# ControllerV1_0_1.net
KiCad netlist of a schematic drawn in Altium Designer
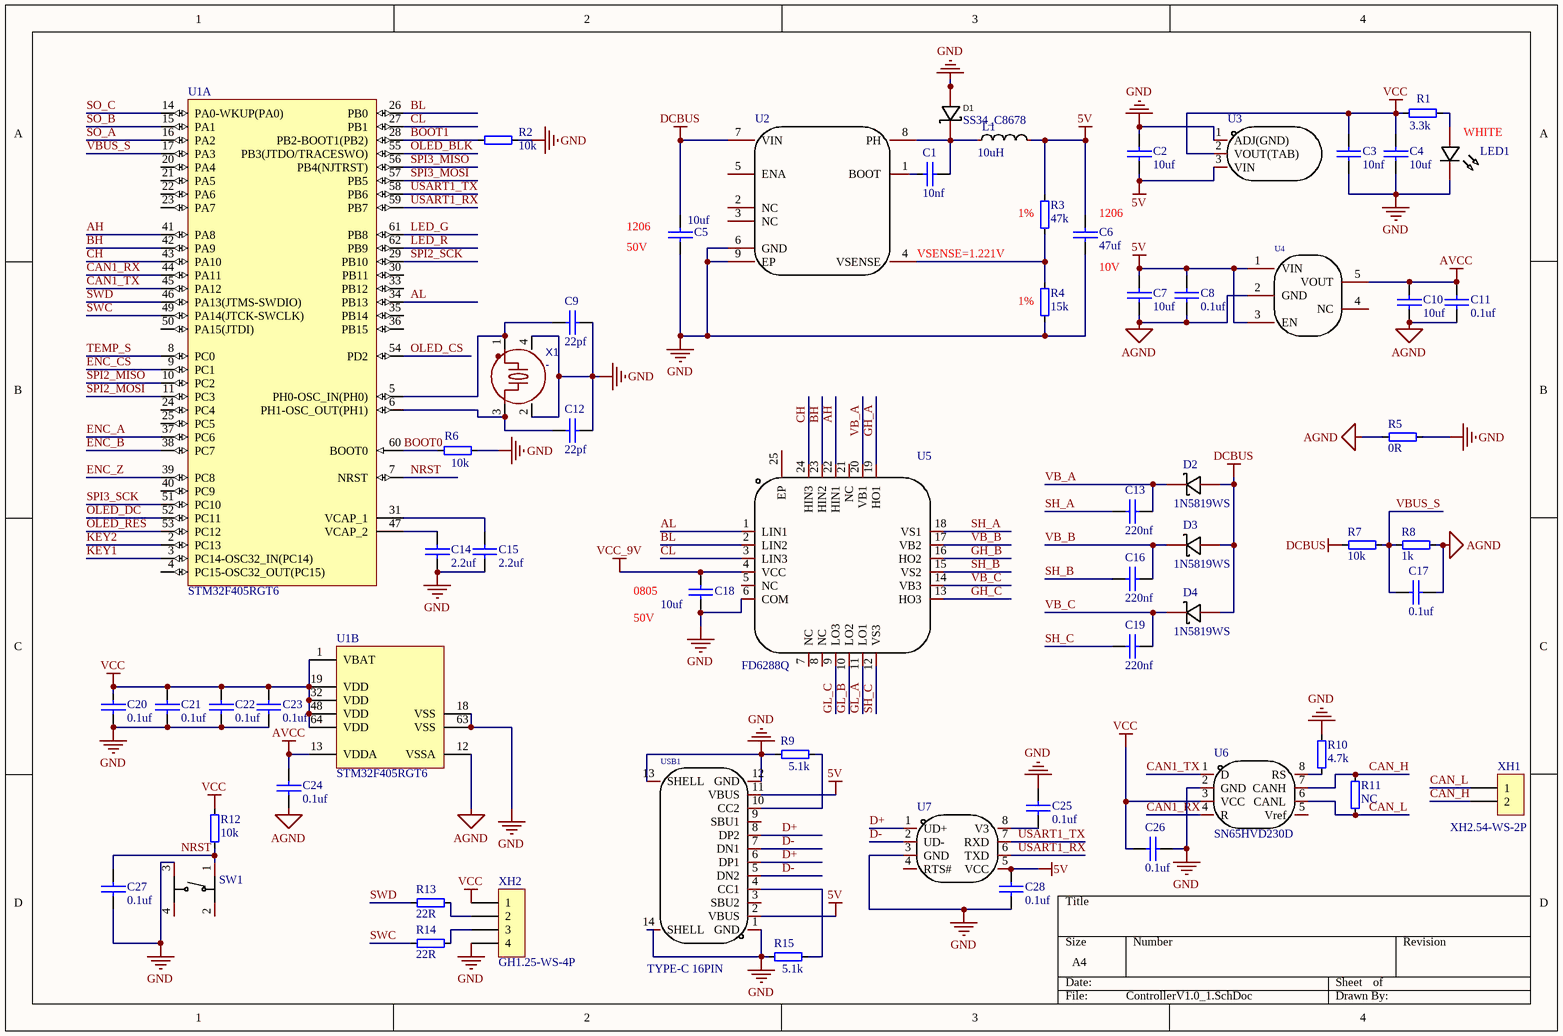
[diagram p0: ControllerV1.0_1.SchDoc]

(export (version "E")
  (design (tool "Eeschema 10.0.6"))
  (components
    (comp (ref "C1")
      (value "10nf")
      (footprint "0603C")
      (description "贴片电容")
      (libsource (lib "Controller") (part "CAP"))
    )
    (comp (ref "C2")
      (value "10uf")
      (footprint "0603C")
      (description "贴片电容")
      (libsource (lib "Controller") (part "CAP"))
    )
    (comp (ref "C3")
      (value "10nf")
      (footprint "0603C")
      (description "贴片电容")
      (libsource (lib "Controller") (part "CAP"))
    )
    (comp (ref "C4")
      (value "10uf")
      (footprint "0603C")
      (description "贴片电容")
      (libsource (lib "Controller") (part "CAP"))
    )
    (comp (ref "C5")
      (value "10uf")
      (footprint "1206C")
      (description "贴片电容")
      (libsource (lib "Controller") (part "CAP"))
    )
    (comp (ref "C6")
      (value "47uf")
      (footprint "1206C")
      (description "贴片电容")
      (libsource (lib "Controller") (part "CAP"))
    )
    (comp (ref "C7")
      (value "10uf")
      (footprint "0603C")
      (description "贴片电容")
      (libsource (lib "Controller") (part "CAP"))
    )
    (comp (ref "C8")
      (value "0.1uf")
      (footprint "0603C")
      (description "贴片电容")
      (libsource (lib "Controller") (part "CAP"))
    )
    (comp (ref "C9")
      (value "22pf")
      (footprint "0603C")
      (description "贴片电容")
      (libsource (lib "Controller") (part "CAP"))
    )
    (comp (ref "C10")
      (value "10uf")
      (footprint "0603C")
      (description "贴片电容")
      (libsource (lib "Controller") (part "CAP"))
    )
    (comp (ref "C11")
      (value "0.1uf")
      (footprint "0603C")
      (description "贴片电容")
      (libsource (lib "Controller") (part "CAP"))
    )
    (comp (ref "C12")
      (value "22pf")
      (footprint "0603C")
      (description "贴片电容")
      (libsource (lib "Controller") (part "CAP"))
    )
    (comp (ref "C13")
      (value "220nf")
      (footprint "0603C")
      (description "贴片电容")
      (libsource (lib "Controller") (part "CAP"))
    )
    (comp (ref "C14")
      (value "2.2uf")
      (footprint "0603C")
      (description "贴片电容")
      (libsource (lib "Controller") (part "CAP"))
    )
    (comp (ref "C15")
      (value "2.2uf")
      (footprint "0603C")
      (description "贴片电容")
      (libsource (lib "Controller") (part "CAP"))
    )
    (comp (ref "C16")
      (value "220nf")
      (footprint "0603C")
      (description "贴片电容")
      (libsource (lib "Controller") (part "CAP"))
    )
    (comp (ref "C17")
      (value "0.1uf")
      (footprint "0603C")
      (description "贴片电容")
      (libsource (lib "Controller") (part "CAP"))
    )
    (comp (ref "C18")
      (value "10uf")
      (footprint "0805C")
      (description "贴片电容")
      (libsource (lib "Controller") (part "CAP"))
    )
    (comp (ref "C19")
      (value "220nf")
      (footprint "0603C")
      (description "贴片电容")
      (libsource (lib "Controller") (part "CAP"))
    )
    (comp (ref "C20")
      (value "0.1uf")
      (footprint "0603C")
      (description "贴片电容")
      (libsource (lib "Controller") (part "CAP"))
    )
    (comp (ref "C21")
      (value "0.1uf")
      (footprint "0603C")
      (description "贴片电容")
      (libsource (lib "Controller") (part "CAP"))
    )
    (comp (ref "C22")
      (value "0.1uf")
      (footprint "0603C")
      (description "贴片电容")
      (libsource (lib "Controller") (part "CAP"))
    )
    (comp (ref "C23")
      (value "0.1uf")
      (footprint "0603C")
      (description "贴片电容")
      (libsource (lib "Controller") (part "CAP"))
    )
    (comp (ref "C24")
      (value "0.1uf")
      (footprint "0603C")
      (description "贴片电容")
      (libsource (lib "Controller") (part "CAP"))
    )
    (comp (ref "C25")
      (value "0.1uf")
      (footprint "0603C")
      (description "贴片电容")
      (libsource (lib "Controller") (part "CAP"))
    )
    (comp (ref "C26")
      (value "0.1uf")
      (footprint "0603C")
      (description "贴片电容")
      (libsource (lib "Controller") (part "CAP"))
    )
    (comp (ref "C27")
      (value "0.1uf")
      (footprint "0603C")
      (description "贴片电容")
      (libsource (lib "Controller") (part "CAP"))
    )
    (comp (ref "C28")
      (value "0.1uf")
      (footprint "0603C")
      (description "贴片电容")
      (libsource (lib "Controller") (part "CAP"))
    )
    (comp (ref "D1")
      (value "SS34_C8678")
      (footprint "SS34")
      (description "肖特基二极管")
      (fields (field (name "MANUFACTURER") "MDD") (field (name "MANUFACTURER PART") "SS34"))
      (libsource (lib "Controller") (part "SS34"))
    )
    (comp (ref "D2")
      (value "1N5819WS")
      (footprint "SOD-323")
      (description "肖特基二极管")
      (fields (field (name "MANUFACTURER") "Hottech(合科泰)"))
      (libsource (lib "Controller") (part "1N5819WS"))
    )
    (comp (ref "D3")
      (value "1N5819WS")
      (footprint "SOD-323")
      (description "肖特基二极管")
      (fields (field (name "MANUFACTURER") "Hottech(合科泰)"))
      (libsource (lib "Controller") (part "1N5819WS"))
    )
    (comp (ref "D4")
      (value "1N5819WS")
      (footprint "SOD-323")
      (description "肖特基二极管")
      (fields (field (name "MANUFACTURER") "Hottech(合科泰)"))
      (libsource (lib "Controller") (part "1N5819WS"))
    )
    (comp (ref "L1")
      (value "10uH")
      (footprint "IND-SMD_L3.0-W3.0_SWPA3010S")
      (description "电感值:10uH;精度:±20%;额定电流:920mA;")
      (fields (field (name "MANUFACTURER") "SXN(顺翔诺)") (field (name "MANUFACTURER PART") "SMDRI74-220M"))
      (libsource (lib "Controller") (part "SWPA3015S100MT"))
    )
    (comp (ref "LED1")
      (value "LED_0603-B")
      (footprint "LED_0603")
      (libsource (lib "Controller") (part "LED"))
    )
    (comp (ref "R1")
      (value "3.3k")
      (footprint "0603R")
      (description "贴片电阻")
      (libsource (lib "Controller") (part "RES"))
    )
    (comp (ref "R2")
      (value "10k")
      (footprint "0603R")
      (description "贴片电阻")
      (libsource (lib "Controller") (part "RES"))
    )
    (comp (ref "R3")
      (value "47k")
      (footprint "0603R")
      (description "贴片电阻")
      (libsource (lib "Controller") (part "RES"))
    )
    (comp (ref "R4")
      (value "15k")
      (footprint "0603R")
      (description "贴片电阻")
      (libsource (lib "Controller") (part "RES"))
    )
    (comp (ref "R5")
      (value "0R")
      (footprint "0603R")
      (description "贴片电阻")
      (libsource (lib "Controller") (part "RES"))
    )
    (comp (ref "R6")
      (value "10k")
      (footprint "0603R")
      (description "贴片电阻")
      (libsource (lib "Controller") (part "RES"))
    )
    (comp (ref "R7")
      (value "10k")
      (footprint "0603R")
      (description "贴片电阻")
      (libsource (lib "Controller") (part "RES"))
    )
    (comp (ref "R8")
      (value "1k")
      (footprint "0603R")
      (description "贴片电阻")
      (libsource (lib "Controller") (part "RES"))
    )
    (comp (ref "R9")
      (value "5.1k")
      (footprint "0603R")
      (description "贴片电阻")
      (libsource (lib "Controller") (part "RES"))
    )
    (comp (ref "R10")
      (value "4.7k")
      (footprint "0603R")
      (description "贴片电阻")
      (libsource (lib "Controller") (part "RES"))
    )
    (comp (ref "R11")
      (value "NC")
      (footprint "0603R")
      (description "贴片电阻")
      (libsource (lib "Controller") (part "RES"))
    )
    (comp (ref "R12")
      (value "10k")
      (footprint "0603R")
      (description "贴片电阻")
      (libsource (lib "Controller") (part "RES"))
    )
    (comp (ref "R13")
      (value "22R")
      (footprint "0603R")
      (description "贴片电阻")
      (libsource (lib "Controller") (part "RES"))
    )
    (comp (ref "R14")
      (value "22R")
      (footprint "0603R")
      (description "贴片电阻")
      (libsource (lib "Controller") (part "RES"))
    )
    (comp (ref "R15")
      (value "5.1k")
      (footprint "0603R")
      (description "贴片电阻")
      (libsource (lib "Controller") (part "RES"))
    )
    (comp (ref "SW1")
      (value "TS-1187A-B-A-B")
      (footprint "TSW SMD-4*4*1.5")
      (description "轻触开关")
      (fields (field (name "MANUFACTURER") "XKB Connectivity(中国星坤)"))
      (libsource (lib "Controller") (part "TS-1187A-B-A-B"))
    )
    (comp (ref "U1")
      (value "STM32F405RGT6")
      (footprint "LQFP_64")
      (fields (field (name "MANUFACTURER") "STMicroelectronics"))
      (libsource (lib "Controller") (part "STM32F405RGT6"))
    )
    (comp (ref "U2")
      (value "TPS5450DDAR")
      (footprint "SOP-8-EP")
      (fields (field (name "MANUFACTURER") "TI(德州仪器)"))
      (libsource (lib "Controller") (part "TPS5450DDAR"))
    )
    (comp (ref "U3")
      (value "AMS1117-3.3_C347256")
      (footprint "SOT-89")
      (description "输出类型:固定;输出极性:正;最大输入电压:18V;输出电压:3.3V;输出电流:1A;电源纹波抑制比(PSRR):60dB@(120Hz);")
      (fields (field (name "MANUFACTURER") "UMW(友台半导体)") (field (name "MANUFACTURER PART") "AMS1117-3.3"))
      (libsource (lib "Controller") (part "AMS1117-3.3_C347256"))
    )
    (comp (ref "U4")
      (value "RT9013-33GB")
      (footprint "SOT-23-5")
      (description "输出类型:固定;输出极性:正;最大输入电压:5.5V;输出电压:3.3V;输出电流:500mA;电源纹波抑制比(PSRR):50dB@(10kHz);")
      (fields (field (name "MANUFACTURER") "RICHTEK(立锜)"))
      (libsource (lib "Controller") (part "RT9013-33GB"))
    )
    (comp (ref "U5")
      (value "FD6288Q")
      (footprint "QFN-24-EP(4x4)")
      (fields (field (name "MANUFACTURER") "Fortior Tech(峰岹)"))
      (libsource (lib "Controller") (part "FD6288Q"))
    )
    (comp (ref "U6")
      (value "SN65HVD230D")
      (footprint "SOP-8")
      (description "具有待机模式的 3.3V CAN 收发器 8-SOIC -40 to 85")
      (fields (field (name "MANUFACTURER") "TI(德州仪器)"))
      (libsource (lib "Controller") (part "SN65HVD230D"))
    )
    (comp (ref "U7")
      (value "CH340N")
      (footprint "SOP-8")
      (fields (field (name "MANUFACTURER") "WCH(南京沁恒)"))
      (libsource (lib "Controller") (part "CH340N"))
    )
    (comp (ref "USB1")
      (value "TYPE-C 16PIN")
      (footprint "USB-C-SMD_TYPE-C-6PIN-2MD-073")
      (description "连接器类型:Type-C;标准:-;公母:母座;触点数量:16;端口数量:1;安装方式:卧贴;额定电流 - 电源:5A;工作温度范围:-25℃~+85℃;")
      (fields
        (field (name "MANUFACTURER") "SHOU HAN(首韩)")
        (field (name "MANUFACTURER PART") "TYPE-C 16PIN 2MD(073)")
      )
      (libsource (lib "Controller") (part "TYPE-C 16PIN 2MD(073)"))
    )
    (comp (ref "X1")
      (value "-")
      (footprint "OSC 2520-4P")
      (description "8MHz")
      (fields
        (field (name "BOM_SUPPLIER PART") "C843260")
        (field (name "BOM_MANUFACTURER PART") "NX2016SA-32MHZ-STD-CZS-5")
        (field (name "CONTRIBUTOR") "LCSC")
      )
      (libsource (lib "Controller") (part "四脚晶振"))
    )
    (comp (ref "XH1")
      (value "XH2.54-WS-2P")
      (footprint "XH2.54-WS-2P")
      (libsource (lib "Controller") (part "XH2.54-WS-2P"))
    )
    (comp (ref "XH2")
      (value "GH1.25-WS-4P")
      (footprint "GH1.25-WS-4P")
      (libsource (lib "Controller") (part "GH1.25-WS-4P"))
    )
  )
  (nets
    (net (code "1") (name "/AH") (class "Default")
      (node (ref "U1") (pin "41") (pinfunction "PA8_41") (pintype "bidirectional"))
      (node (ref "U5") (pin "22") (pinfunction "HIN1_22") (pintype "passive"))
    )
    (net (code "2") (name "/AL") (class "Default")
      (node (ref "U1") (pin "34") (pinfunction "PB13_34") (pintype "bidirectional"))
      (node (ref "U5") (pin "1") (pinfunction "LIN1_1") (pintype "passive"))
    )
    (net (code "3") (name "/BH") (class "Default")
      (node (ref "U1") (pin "42") (pinfunction "PA9_42") (pintype "bidirectional"))
      (node (ref "U5") (pin "23") (pinfunction "HIN2_23") (pintype "passive"))
    )
    (net (code "4") (name "/BL") (class "Default")
      (node (ref "U1") (pin "26") (pinfunction "PB0_26") (pintype "bidirectional"))
      (node (ref "U5") (pin "2") (pinfunction "LIN2_2") (pintype "passive"))
    )
    (net (code "5") (name "/BOOT0") (class "Default")
      (node (ref "R6") (pin "1") (pinfunction "1_1") (pintype "passive"))
      (node (ref "U1") (pin "60") (pinfunction "BOOT0_60") (pintype "input"))
    )
    (net (code "6") (name "/BOOT1") (class "Default")
      (node (ref "R2") (pin "1") (pinfunction "1_1") (pintype "passive"))
      (node (ref "U1") (pin "28") (pinfunction "PB2-BOOT1(PB2)_28") (pintype "bidirectional"))
    )
    (net (code "7") (name "/CAN1_RX") (class "Default")
      (node (ref "U1") (pin "44") (pinfunction "PA11_44") (pintype "bidirectional"))
      (node (ref "U6") (pin "4") (pinfunction "R_4") (pintype "passive"))
    )
    (net (code "8") (name "/CAN1_TX") (class "Default")
      (node (ref "U1") (pin "45") (pinfunction "PA12_45") (pintype "bidirectional"))
      (node (ref "U6") (pin "1") (pinfunction "D_1") (pintype "passive"))
    )
    (net (code "9") (name "/CAN_H") (class "Default")
      (node (ref "R11") (pin "2") (pinfunction "2_2") (pintype "passive"))
      (node (ref "U6") (pin "7") (pinfunction "CANH_7") (pintype "passive"))
      (node (ref "XH1") (pin "2") (pinfunction "2_2") (pintype "passive"))
    )
    (net (code "10") (name "/CAN_L") (class "Default")
      (node (ref "R11") (pin "1") (pinfunction "1_1") (pintype "passive"))
      (node (ref "U6") (pin "6") (pinfunction "CANL_6") (pintype "passive"))
      (node (ref "XH1") (pin "1") (pinfunction "1_1") (pintype "passive"))
    )
    (net (code "11") (name "/CH") (class "Default")
      (node (ref "U1") (pin "43") (pinfunction "PA10_43") (pintype "bidirectional"))
      (node (ref "U5") (pin "24") (pinfunction "HIN3_24") (pintype "passive"))
    )
    (net (code "12") (name "/CL") (class "Default")
      (node (ref "U1") (pin "27") (pinfunction "PB1_27") (pintype "bidirectional"))
      (node (ref "U5") (pin "3") (pinfunction "LIN3_3") (pintype "passive"))
    )
    (net (code "13") (name "/D+") (class "Default")
      (node (ref "U7") (pin "1") (pinfunction "UD+_1") (pintype "passive"))
      (node (ref "USB1") (pin "6") (pinfunction "DP1_6") (pintype "passive"))
      (node (ref "USB1") (pin "8") (pinfunction "DP2_8") (pintype "passive"))
    )
    (net (code "14") (name "/D-") (class "Default")
      (node (ref "U7") (pin "2") (pinfunction "UD-_2") (pintype "passive"))
      (node (ref "USB1") (pin "5") (pinfunction "DN2_5") (pintype "passive"))
      (node (ref "USB1") (pin "7") (pinfunction "DN1_7") (pintype "passive"))
    )
    (net (code "15") (name "/ENC_A") (class "Default")
      (node (ref "U1") (pin "37") (pinfunction "PC6_37") (pintype "bidirectional"))
    )
    (net (code "16") (name "/ENC_B") (class "Default")
      (node (ref "U1") (pin "38") (pinfunction "PC7_38") (pintype "bidirectional"))
    )
    (net (code "17") (name "/ENC_CS") (class "Default")
      (node (ref "U1") (pin "9") (pinfunction "PC1_9") (pintype "bidirectional"))
    )
    (net (code "18") (name "/ENC_Z") (class "Default")
      (node (ref "U1") (pin "39") (pinfunction "PC8_39") (pintype "bidirectional"))
    )
    (net (code "19") (name "/GH_A") (class "Default")
      (node (ref "U5") (pin "19") (pinfunction "HO1_19") (pintype "passive"))
    )
    (net (code "20") (name "/GH_B") (class "Default")
      (node (ref "U5") (pin "16") (pinfunction "HO2_16") (pintype "passive"))
    )
    (net (code "21") (name "/GH_C") (class "Default")
      (node (ref "U5") (pin "13") (pinfunction "HO3_13") (pintype "passive"))
    )
    (net (code "22") (name "/GL_A") (class "Default")
      (node (ref "U5") (pin "11") (pinfunction "LO1_11") (pintype "passive"))
    )
    (net (code "23") (name "/GL_B") (class "Default")
      (node (ref "U5") (pin "10") (pinfunction "LO2_10") (pintype "passive"))
    )
    (net (code "24") (name "/GL_C") (class "Default")
      (node (ref "U5") (pin "9") (pinfunction "LO3_9") (pintype "passive"))
    )
    (net (code "25") (name "/KEY1") (class "Default")
      (node (ref "U1") (pin "3") (pinfunction "PC14-OSC32_IN(PC14)_3") (pintype "bidirectional"))
    )
    (net (code "26") (name "/KEY2") (class "Default")
      (node (ref "U1") (pin "2") (pinfunction "PC13_2") (pintype "bidirectional"))
    )
    (net (code "27") (name "/LED_G") (class "Default")
      (node (ref "U1") (pin "61") (pinfunction "PB8_61") (pintype "bidirectional"))
    )
    (net (code "28") (name "/LED_R") (class "Default")
      (node (ref "U1") (pin "62") (pinfunction "PB9_62") (pintype "bidirectional"))
    )
    (net (code "29") (name "/NRST") (class "Default")
      (node (ref "C27") (pin "1") (pinfunction "1_1") (pintype "passive"))
      (node (ref "R12") (pin "1") (pinfunction "1_1") (pintype "passive"))
      (node (ref "SW1") (pin "1") (pinfunction "A_1") (pintype "passive"))
      (node (ref "U1") (pin "7") (pinfunction "NRST_7") (pintype "bidirectional"))
    )
    (net (code "30") (name "/OLED_BLK") (class "Default")
      (node (ref "U1") (pin "55") (pinfunction "PB3(JTDO/TRACESWO)_55") (pintype "bidirectional"))
    )
    (net (code "31") (name "/OLED_CS") (class "Default")
      (node (ref "U1") (pin "54") (pinfunction "PD2_54") (pintype "bidirectional"))
    )
    (net (code "32") (name "/OLED_DC") (class "Default")
      (node (ref "U1") (pin "52") (pinfunction "PC11_52") (pintype "bidirectional"))
    )
    (net (code "33") (name "/OLED_RES") (class "Default")
      (node (ref "U1") (pin "53") (pinfunction "PC12_53") (pintype "bidirectional"))
    )
    (net (code "34") (name "/SH_A") (class "Default")
      (node (ref "C13") (pin "1") (pinfunction "1_1") (pintype "passive"))
      (node (ref "U5") (pin "18") (pinfunction "VS1_18") (pintype "passive"))
    )
    (net (code "35") (name "/SH_B") (class "Default")
      (node (ref "C16") (pin "1") (pinfunction "1_1") (pintype "passive"))
      (node (ref "U5") (pin "15") (pinfunction "VS2_15") (pintype "passive"))
    )
    (net (code "36") (name "/SH_C") (class "Default")
      (node (ref "C19") (pin "1") (pinfunction "1_1") (pintype "passive"))
      (node (ref "U5") (pin "12") (pinfunction "VS3_12") (pintype "passive"))
    )
    (net (code "37") (name "/SO_A") (class "Default")
      (node (ref "U1") (pin "16") (pinfunction "PA2_16") (pintype "bidirectional"))
    )
    (net (code "38") (name "/SO_B") (class "Default")
      (node (ref "U1") (pin "15") (pinfunction "PA1_15") (pintype "bidirectional"))
    )
    (net (code "39") (name "/SO_C") (class "Default")
      (node (ref "U1") (pin "14") (pinfunction "PA0-WKUP(PA0)_14") (pintype "bidirectional"))
    )
    (net (code "40") (name "/SPI2_MISO") (class "Default")
      (node (ref "U1") (pin "10") (pinfunction "PC2_10") (pintype "bidirectional"))
    )
    (net (code "41") (name "/SPI2_MOSI") (class "Default")
      (node (ref "U1") (pin "11") (pinfunction "PC3_11") (pintype "bidirectional"))
    )
    (net (code "42") (name "/SPI2_SCK") (class "Default")
      (node (ref "U1") (pin "29") (pinfunction "PB10_29") (pintype "bidirectional"))
    )
    (net (code "43") (name "/SPI3_MISO") (class "Default")
      (node (ref "U1") (pin "56") (pinfunction "PB4(NJTRST)_56") (pintype "bidirectional"))
    )
    (net (code "44") (name "/SPI3_MOSI") (class "Default")
      (node (ref "U1") (pin "57") (pinfunction "PB5_57") (pintype "bidirectional"))
    )
    (net (code "45") (name "/SPI3_SCK") (class "Default")
      (node (ref "U1") (pin "51") (pinfunction "PC10_51") (pintype "bidirectional"))
    )
    (net (code "46") (name "/SWC") (class "Default")
      (node (ref "R14") (pin "1") (pinfunction "1_1") (pintype "passive"))
      (node (ref "U1") (pin "49") (pinfunction "PA14(JTCK-SWCLK)_49") (pintype "bidirectional"))
    )
    (net (code "47") (name "/SWD") (class "Default")
      (node (ref "R13") (pin "1") (pinfunction "1_1") (pintype "passive"))
      (node (ref "U1") (pin "46") (pinfunction "PA13(JTMS-SWDIO)_46") (pintype "bidirectional"))
    )
    (net (code "48") (name "/TEMP_S") (class "Default")
      (node (ref "U1") (pin "8") (pinfunction "PC0_8") (pintype "bidirectional"))
    )
    (net (code "49") (name "/USART1_RX") (class "Default")
      (node (ref "U1") (pin "59") (pinfunction "PB7_59") (pintype "bidirectional"))
      (node (ref "U7") (pin "6") (pinfunction "TXD_6") (pintype "passive"))
    )
    (net (code "50") (name "/USART1_TX") (class "Default")
      (node (ref "U1") (pin "58") (pinfunction "PB6_58") (pintype "bidirectional"))
      (node (ref "U7") (pin "7") (pinfunction "RXD_7") (pintype "passive"))
    )
    (net (code "51") (name "/VBUS_S") (class "Default")
      (node (ref "C17") (pin "1") (pinfunction "1_1") (pintype "passive"))
      (node (ref "R7") (pin "1") (pinfunction "1_1") (pintype "passive"))
      (node (ref "R8") (pin "2") (pinfunction "2_2") (pintype "passive"))
      (node (ref "U1") (pin "17") (pinfunction "PA3_17") (pintype "bidirectional"))
    )
    (net (code "52") (name "/VB_A") (class "Default")
      (node (ref "C13") (pin "2") (pinfunction "2_2") (pintype "passive"))
      (node (ref "D2") (pin "1") (pinfunction "K_1") (pintype "passive"))
      (node (ref "U5") (pin "20") (pinfunction "VB1_20") (pintype "passive"))
    )
    (net (code "53") (name "/VB_B") (class "Default")
      (node (ref "C16") (pin "2") (pinfunction "2_2") (pintype "passive"))
      (node (ref "D3") (pin "1") (pinfunction "K_1") (pintype "passive"))
      (node (ref "U5") (pin "17") (pinfunction "VB2_17") (pintype "passive"))
    )
    (net (code "54") (name "/VB_C") (class "Default")
      (node (ref "C19") (pin "2") (pinfunction "2_2") (pintype "passive"))
      (node (ref "D4") (pin "1") (pinfunction "K_1") (pintype "passive"))
      (node (ref "U5") (pin "14") (pinfunction "VB3_14") (pintype "passive"))
    )
    (net (code "55") (name "5V") (class "Default")
      (node (ref "C2") (pin "2") (pinfunction "2_2") (pintype "passive"))
      (node (ref "C28") (pin "1") (pinfunction "1_1") (pintype "passive"))
      (node (ref "C6") (pin "1") (pinfunction "1_1") (pintype "passive"))
      (node (ref "C7") (pin "1") (pinfunction "1_1") (pintype "passive"))
      (node (ref "C8") (pin "1") (pinfunction "1_1") (pintype "passive"))
      (node (ref "L1") (pin "2") (pinfunction "2_2") (pintype "passive"))
      (node (ref "R3") (pin "2") (pinfunction "2_2") (pintype "passive"))
      (node (ref "U3") (pin "3") (pinfunction "VIN_3") (pintype "passive"))
      (node (ref "U4") (pin "1") (pinfunction "VIN_1") (pintype "passive"))
      (node (ref "U4") (pin "3") (pinfunction "EN_3") (pintype "passive"))
      (node (ref "U7") (pin "5") (pinfunction "VCC_5") (pintype "passive"))
      (node (ref "USB1") (pin "11") (pinfunction "VBUS_11") (pintype "passive"))
      (node (ref "USB1") (pin "2") (pinfunction "VBUS_2") (pintype "passive"))
    )
    (net (code "56") (name "AGND") (class "Default")
      (node (ref "C10") (pin "2") (pinfunction "2_2") (pintype "passive"))
      (node (ref "C11") (pin "2") (pinfunction "2_2") (pintype "passive"))
      (node (ref "C17") (pin "2") (pinfunction "2_2") (pintype "passive"))
      (node (ref "C24") (pin "2") (pinfunction "2_2") (pintype "passive"))
      (node (ref "C7") (pin "2") (pinfunction "2_2") (pintype "passive"))
      (node (ref "C8") (pin "2") (pinfunction "2_2") (pintype "passive"))
      (node (ref "R5") (pin "2") (pinfunction "2_2") (pintype "passive"))
      (node (ref "R8") (pin "1") (pinfunction "1_1") (pintype "passive"))
      (node (ref "U1") (pin "12") (pinfunction "VSSA_12") (pintype "power_in"))
      (node (ref "U4") (pin "2") (pinfunction "GND_2") (pintype "passive"))
    )
    (net (code "57") (name "AVCC") (class "Default")
      (node (ref "C10") (pin "1") (pinfunction "1_1") (pintype "passive"))
      (node (ref "C11") (pin "1") (pinfunction "1_1") (pintype "passive"))
      (node (ref "C24") (pin "1") (pinfunction "1_1") (pintype "passive"))
      (node (ref "U1") (pin "13") (pinfunction "VDDA_13") (pintype "power_in"))
      (node (ref "U4") (pin "5") (pinfunction "VOUT_5") (pintype "passive"))
    )
    (net (code "58") (name "DCBUS") (class "Default")
      (node (ref "C5") (pin "1") (pinfunction "1_1") (pintype "passive"))
      (node (ref "D2") (pin "2") (pinfunction "A_2") (pintype "passive"))
      (node (ref "D3") (pin "2") (pinfunction "A_2") (pintype "passive"))
      (node (ref "D4") (pin "2") (pinfunction "A_2") (pintype "passive"))
      (node (ref "R7") (pin "2") (pinfunction "2_2") (pintype "passive"))
      (node (ref "U2") (pin "7") (pinfunction "VIN_7") (pintype "passive"))
    )
    (net (code "59") (name "GND") (class "Default")
      (node (ref "C12") (pin "2") (pinfunction "2_2") (pintype "passive"))
      (node (ref "C14") (pin "2") (pinfunction "2_2") (pintype "passive"))
      (node (ref "C15") (pin "2") (pinfunction "2_2") (pintype "passive"))
      (node (ref "C18") (pin "2") (pinfunction "2_2") (pintype "passive"))
      (node (ref "C2") (pin "1") (pinfunction "1_1") (pintype "passive"))
      (node (ref "C20") (pin "2") (pinfunction "2_2") (pintype "passive"))
      (node (ref "C21") (pin "2") (pinfunction "2_2") (pintype "passive"))
      (node (ref "C22") (pin "2") (pinfunction "2_2") (pintype "passive"))
      (node (ref "C23") (pin "2") (pinfunction "2_2") (pintype "passive"))
      (node (ref "C25") (pin "2") (pinfunction "2_2") (pintype "passive"))
      (node (ref "C26") (pin "2") (pinfunction "2_2") (pintype "passive"))
      (node (ref "C27") (pin "2") (pinfunction "2_2") (pintype "passive"))
      (node (ref "C28") (pin "2") (pinfunction "2_2") (pintype "passive"))
      (node (ref "C3") (pin "2") (pinfunction "2_2") (pintype "passive"))
      (node (ref "C4") (pin "2") (pinfunction "2_2") (pintype "passive"))
      (node (ref "C5") (pin "2") (pinfunction "2_2") (pintype "passive"))
      (node (ref "C6") (pin "2") (pinfunction "2_2") (pintype "passive"))
      (node (ref "C9") (pin "2") (pinfunction "2_2") (pintype "passive"))
      (node (ref "D1") (pin "2") (pinfunction "A_2") (pintype "passive"))
      (node (ref "LED1") (pin "1") (pinfunction "C_1") (pintype "passive"))
      (node (ref "R10") (pin "2") (pinfunction "2_2") (pintype "passive"))
      (node (ref "R15") (pin "1") (pinfunction "1_1") (pintype "passive"))
      (node (ref "R2") (pin "2") (pinfunction "2_2") (pintype "passive"))
      (node (ref "R4") (pin "1") (pinfunction "1_1") (pintype "passive"))
      (node (ref "R5") (pin "1") (pinfunction "1_1") (pintype "passive"))
      (node (ref "R6") (pin "2") (pinfunction "2_2") (pintype "passive"))
      (node (ref "R9") (pin "1") (pinfunction "1_1") (pintype "passive"))
      (node (ref "SW1") (pin "3") (pinfunction "C_3") (pintype "passive"))
      (node (ref "U1") (pin "18") (pinfunction "VSS_18") (pintype "power_in"))
      (node (ref "U1") (pin "63") (pinfunction "VSS_63") (pintype "power_in"))
      (node (ref "U2") (pin "6") (pinfunction "GND_6") (pintype "passive"))
      (node (ref "U2") (pin "9") (pinfunction "EP_9") (pintype "passive"))
      (node (ref "U3") (pin "1") (pinfunction "ADJ(GND)_1") (pintype "passive"))
      (node (ref "U5") (pin "6") (pinfunction "COM_6") (pintype "passive"))
      (node (ref "U6") (pin "2") (pinfunction "GND_2") (pintype "passive"))
      (node (ref "U7") (pin "3") (pinfunction "GND_3") (pintype "passive"))
      (node (ref "USB1") (pin "1") (pinfunction "GND_1") (pintype "passive"))
      (node (ref "USB1") (pin "12") (pinfunction "GND_12") (pintype "passive"))
      (node (ref "USB1") (pin "13") (pinfunction "SHELL_13") (pintype "passive"))
      (node (ref "USB1") (pin "14") (pinfunction "SHELL_14") (pintype "passive"))
      (node (ref "X1") (pin "2") (pinfunction "GND_2") (pintype "passive"))
      (node (ref "X1") (pin "4") (pinfunction "GND_4") (pintype "passive"))
      (node (ref "XH2") (pin "4") (pinfunction "4_4") (pintype "passive"))
    )
    (net (code "60") (name "Net-(D1-K)") (class "Default")
      (node (ref "C1") (pin "2") (pinfunction "2_2") (pintype "passive"))
      (node (ref "D1") (pin "1") (pinfunction "K_1") (pintype "passive"))
      (node (ref "L1") (pin "1") (pinfunction "1_1") (pintype "passive"))
      (node (ref "U2") (pin "8") (pinfunction "PH_8") (pintype "passive"))
    )
    (net (code "61") (name "Net-(LED1-A)") (class "Default")
      (node (ref "LED1") (pin "2") (pinfunction "A_2") (pintype "passive"))
      (node (ref "R1") (pin "1") (pinfunction "1_1") (pintype "passive"))
    )
    (net (code "62") (name "Net-(R13-Pad2)") (class "Default")
      (node (ref "R13") (pin "2") (pinfunction "2_2") (pintype "passive"))
      (node (ref "XH2") (pin "2") (pinfunction "2_2") (pintype "passive"))
    )
    (net (code "63") (name "Net-(R14-Pad2)") (class "Default")
      (node (ref "R14") (pin "2") (pinfunction "2_2") (pintype "passive"))
      (node (ref "XH2") (pin "3") (pinfunction "3_3") (pintype "passive"))
    )
    (net (code "64") (name "Net-(U1A-PH0-OSC_IN(PH0))") (class "Default")
      (node (ref "C9") (pin "1") (pinfunction "1_1") (pintype "passive"))
      (node (ref "U1") (pin "5") (pinfunction "PH0-OSC_IN(PH0)_5") (pintype "bidirectional"))
      (node (ref "X1") (pin "1") (pinfunction "1_1") (pintype "passive"))
    )
    (net (code "65") (name "Net-(U1A-PH1-OSC_OUT(PH1))") (class "Default")
      (node (ref "C12") (pin "1") (pinfunction "1_1") (pintype "passive"))
      (node (ref "U1") (pin "6") (pinfunction "PH1-OSC_OUT(PH1)_6") (pintype "bidirectional"))
      (node (ref "X1") (pin "3") (pinfunction "3_3") (pintype "passive"))
    )
    (net (code "66") (name "Net-(U1A-VCAP_1)") (class "Default")
      (node (ref "C15") (pin "1") (pinfunction "1_1") (pintype "passive"))
      (node (ref "U1") (pin "31") (pinfunction "VCAP_1_31") (pintype "power_in"))
    )
    (net (code "67") (name "Net-(U1A-VCAP_2)") (class "Default")
      (node (ref "C14") (pin "1") (pinfunction "1_1") (pintype "passive"))
      (node (ref "U1") (pin "47") (pinfunction "VCAP_2_47") (pintype "power_in"))
    )
    (net (code "68") (name "Net-(U2-BOOT)") (class "Default")
      (node (ref "C1") (pin "1") (pinfunction "1_1") (pintype "passive"))
      (node (ref "U2") (pin "1") (pinfunction "BOOT_1") (pintype "passive"))
    )
    (net (code "69") (name "Net-(U2-VSENSE)") (class "Default")
      (node (ref "R3") (pin "1") (pinfunction "1_1") (pintype "passive"))
      (node (ref "R4") (pin "2") (pinfunction "2_2") (pintype "passive"))
      (node (ref "U2") (pin "4") (pinfunction "VSENSE_4") (pintype "passive"))
    )
    (net (code "70") (name "Net-(U6-RS)") (class "Default")
      (node (ref "R10") (pin "1") (pinfunction "1_1") (pintype "passive"))
      (node (ref "U6") (pin "8") (pinfunction "RS_8") (pintype "passive"))
    )
    (net (code "71") (name "Net-(U7-V3)") (class "Default")
      (node (ref "C25") (pin "1") (pinfunction "1_1") (pintype "passive"))
      (node (ref "U7") (pin "8") (pinfunction "V3_8") (pintype "passive"))
    )
    (net (code "72") (name "Net-(USB1-CC1)") (class "Default")
      (node (ref "R15") (pin "2") (pinfunction "2_2") (pintype "passive"))
      (node (ref "USB1") (pin "4") (pinfunction "CC1_4") (pintype "passive"))
    )
    (net (code "73") (name "Net-(USB1-CC2)") (class "Default")
      (node (ref "R9") (pin "2") (pinfunction "2_2") (pintype "passive"))
      (node (ref "USB1") (pin "10") (pinfunction "CC2_10") (pintype "passive"))
    )
    (net (code "74") (name "VCC") (class "Default")
      (node (ref "C20") (pin "1") (pinfunction "1_1") (pintype "passive"))
      (node (ref "C21") (pin "1") (pinfunction "1_1") (pintype "passive"))
      (node (ref "C22") (pin "1") (pinfunction "1_1") (pintype "passive"))
      (node (ref "C23") (pin "1") (pinfunction "1_1") (pintype "passive"))
      (node (ref "C26") (pin "1") (pinfunction "1_1") (pintype "passive"))
      (node (ref "C3") (pin "1") (pinfunction "1_1") (pintype "passive"))
      (node (ref "C4") (pin "1") (pinfunction "1_1") (pintype "passive"))
      (node (ref "R1") (pin "2") (pinfunction "2_2") (pintype "passive"))
      (node (ref "R12") (pin "2") (pinfunction "2_2") (pintype "passive"))
      (node (ref "U1") (pin "1") (pinfunction "VBAT_1") (pintype "power_in"))
      (node (ref "U1") (pin "19") (pinfunction "VDD_19") (pintype "power_in"))
      (node (ref "U1") (pin "32") (pinfunction "VDD_32") (pintype "power_in"))
      (node (ref "U1") (pin "48") (pinfunction "VDD_48") (pintype "power_in"))
      (node (ref "U1") (pin "64") (pinfunction "VDD_64") (pintype "power_in"))
      (node (ref "U3") (pin "2") (pinfunction "VOUT(TAB)_2") (pintype "passive"))
      (node (ref "U6") (pin "3") (pinfunction "VCC_3") (pintype "passive"))
      (node (ref "XH2") (pin "1") (pinfunction "1_1") (pintype "passive"))
    )
    (net (code "75") (name "VCC_9V") (class "Default")
      (node (ref "C18") (pin "1") (pinfunction "1_1") (pintype "passive"))
      (node (ref "U5") (pin "4") (pinfunction "VCC_4") (pintype "passive"))
    )
    (net (code "76") (name "unconnected-(SW1-B-Pad2)") (class "Default")
      (node (ref "SW1") (pin "2") (pinfunction "B_2") (pintype "passive"))
    )
    (net (code "77") (name "unconnected-(SW1-D-Pad4)") (class "Default")
      (node (ref "SW1") (pin "4") (pinfunction "D_4") (pintype "passive"))
    )
    (net (code "78") (name "unconnected-(U1A-PA4-Pad20)") (class "Default")
      (node (ref "U1") (pin "20") (pinfunction "PA4_20") (pintype "bidirectional"))
    )
    (net (code "79") (name "unconnected-(U1A-PA5-Pad21)") (class "Default")
      (node (ref "U1") (pin "21") (pinfunction "PA5_21") (pintype "bidirectional"))
    )
    (net (code "80") (name "unconnected-(U1A-PA6-Pad22)") (class "Default")
      (node (ref "U1") (pin "22") (pinfunction "PA6_22") (pintype "bidirectional"))
    )
    (net (code "81") (name "unconnected-(U1A-PA7-Pad23)") (class "Default")
      (node (ref "U1") (pin "23") (pinfunction "PA7_23") (pintype "bidirectional"))
    )
    (net (code "82") (name "unconnected-(U1A-PA15(JTDI)-Pad50)") (class "Default")
      (node (ref "U1") (pin "50") (pinfunction "PA15(JTDI)_50") (pintype "bidirectional"))
    )
    (net (code "83") (name "unconnected-(U1A-PB11-Pad30)") (class "Default")
      (node (ref "U1") (pin "30") (pinfunction "PB11_30") (pintype "bidirectional"))
    )
    (net (code "84") (name "unconnected-(U1A-PB12-Pad33)") (class "Default")
      (node (ref "U1") (pin "33") (pinfunction "PB12_33") (pintype "bidirectional"))
    )
    (net (code "85") (name "unconnected-(U1A-PB14-Pad35)") (class "Default")
      (node (ref "U1") (pin "35") (pinfunction "PB14_35") (pintype "bidirectional"))
    )
    (net (code "86") (name "unconnected-(U1A-PB15-Pad36)") (class "Default")
      (node (ref "U1") (pin "36") (pinfunction "PB15_36") (pintype "bidirectional"))
    )
    (net (code "87") (name "unconnected-(U1A-PC4-Pad24)") (class "Default")
      (node (ref "U1") (pin "24") (pinfunction "PC4_24") (pintype "bidirectional"))
    )
    (net (code "88") (name "unconnected-(U1A-PC5-Pad25)") (class "Default")
      (node (ref "U1") (pin "25") (pinfunction "PC5_25") (pintype "bidirectional"))
    )
    (net (code "89") (name "unconnected-(U1A-PC9-Pad40)") (class "Default")
      (node (ref "U1") (pin "40") (pinfunction "PC9_40") (pintype "bidirectional"))
    )
    (net (code "90") (name "unconnected-(U1A-PC15-OSC32_OUT(PC15)-Pad4)") (class "Default")
      (node (ref "U1") (pin "4") (pinfunction "PC15-OSC32_OUT(PC15)_4") (pintype "bidirectional"))
    )
    (net (code "91") (name "unconnected-(U2-ENA-Pad5)") (class "Default")
      (node (ref "U2") (pin "5") (pinfunction "ENA_5") (pintype "passive"))
    )
    (net (code "92") (name "unconnected-(U2-NC-Pad2)") (class "Default")
      (node (ref "U2") (pin "2") (pinfunction "NC_2") (pintype "passive"))
    )
    (net (code "93") (name "unconnected-(U2-NC-Pad3)") (class "Default")
      (node (ref "U2") (pin "3") (pinfunction "NC_3") (pintype "passive"))
    )
    (net (code "94") (name "unconnected-(U4-NC-Pad4)") (class "Default")
      (node (ref "U4") (pin "4") (pinfunction "NC_4") (pintype "passive"))
    )
    (net (code "95") (name "unconnected-(U5-EP-Pad25)") (class "Default")
      (node (ref "U5") (pin "25") (pinfunction "EP_25") (pintype "passive"))
    )
    (net (code "96") (name "unconnected-(U5-NC-Pad5)") (class "Default")
      (node (ref "U5") (pin "5") (pinfunction "NC_5") (pintype "passive"))
    )
    (net (code "97") (name "unconnected-(U5-NC-Pad7)") (class "Default")
      (node (ref "U5") (pin "7") (pinfunction "NC_7") (pintype "passive"))
    )
    (net (code "98") (name "unconnected-(U5-NC-Pad8)") (class "Default")
      (node (ref "U5") (pin "8") (pinfunction "NC_8") (pintype "passive"))
    )
    (net (code "99") (name "unconnected-(U5-NC-Pad21)") (class "Default")
      (node (ref "U5") (pin "21") (pinfunction "NC_21") (pintype "passive"))
    )
    (net (code "100") (name "unconnected-(U6-Vref-Pad5)") (class "Default")
      (node (ref "U6") (pin "5") (pinfunction "Vref_5") (pintype "passive"))
    )
    (net (code "101") (name "unconnected-(U7-RTS#-Pad4)") (class "Default")
      (node (ref "U7") (pin "4") (pinfunction "RTS#_4") (pintype "passive"))
    )
    (net (code "102") (name "unconnected-(USB1-SBU1-Pad9)") (class "Default")
      (node (ref "USB1") (pin "9") (pinfunction "SBU1_9") (pintype "passive"))
    )
    (net (code "103") (name "unconnected-(USB1-SBU2-Pad3)") (class "Default")
      (node (ref "USB1") (pin "3") (pinfunction "SBU2_3") (pintype "passive"))
    )
  )
)
